# 05_MICROSD.net
KiCad netlist of a schematic drawn in Altium Designer
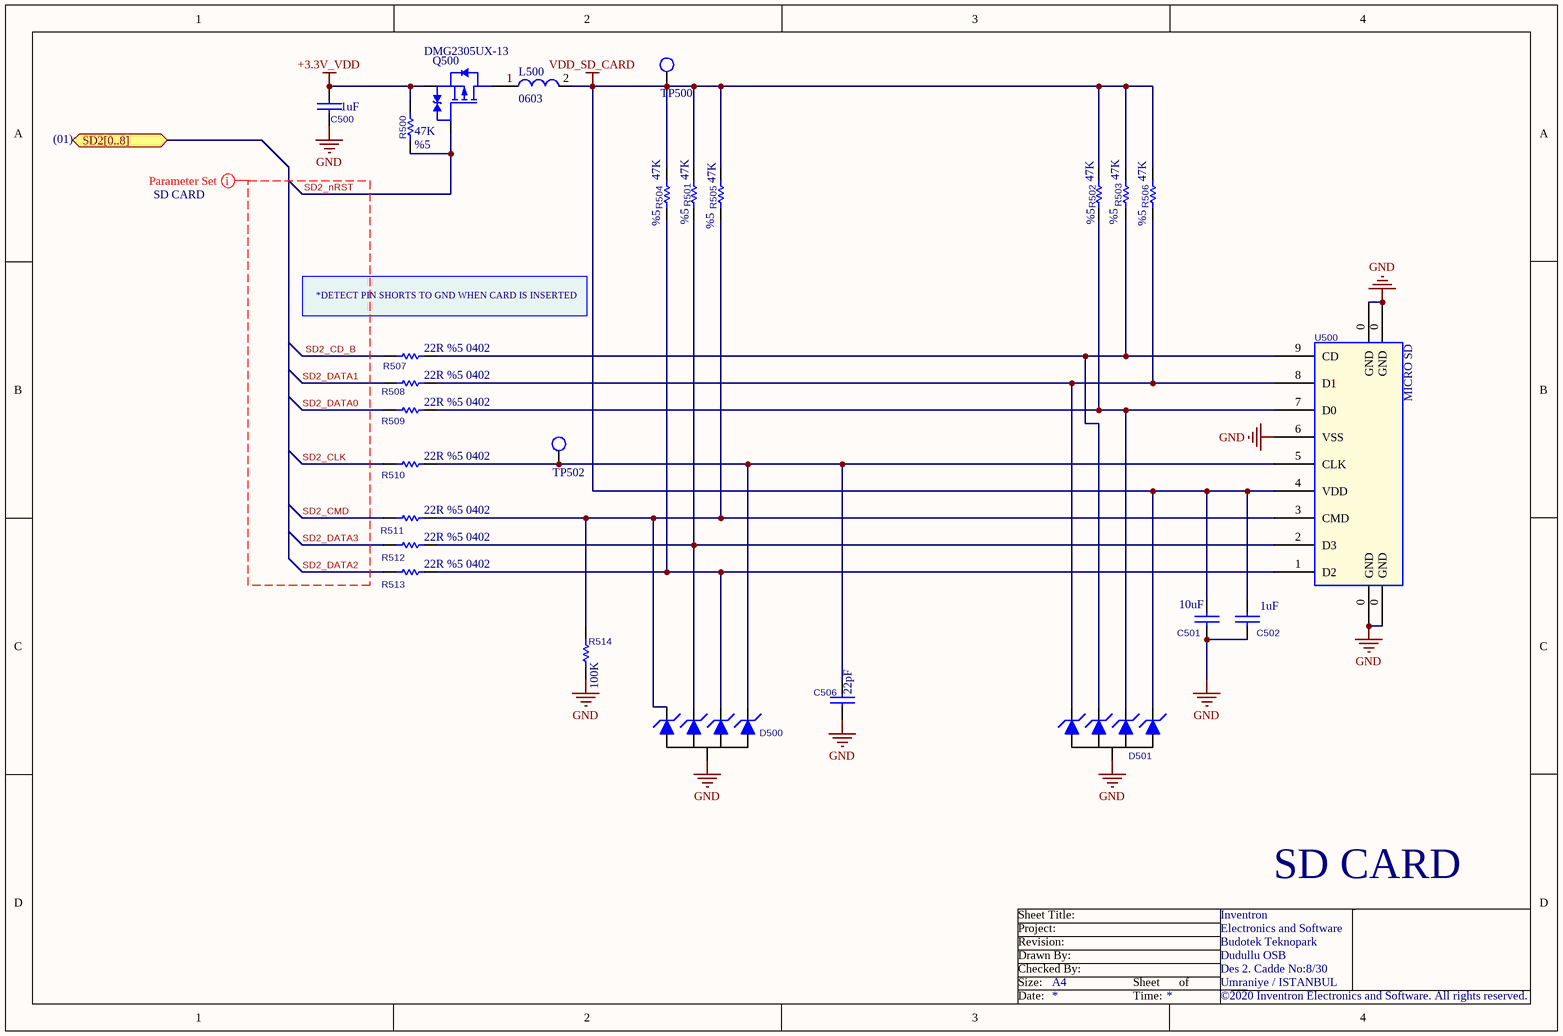
[diagram p0: 05 MICROSD.SchDoc]

(export (version "E")
  (design (tool "Eeschema 10.0.6"))
  (components
    (comp (ref "C500")
      (value "1uF")
      (footprint "0603_CC")
      (description "CAP CER 1UF 25V X7R 0603")
      (fields (field (name "CREATED BY") "LA") (field (name "CHECKED BY") "*"))
      (libsource (lib "ARETE_SCH") (part "CAP-CL10B105KA8NNNC"))
    )
    (comp (ref "C501")
      (value "10uF")
      (footprint "0603_CC")
      (description "CAP CER 10UF 6.3V X6S 0603")
      (fields (field (name "CREATED BY") "LA") (field (name "CHECKED BY") "*"))
      (libsource (lib "ARETE_SCH") (part "CAP-JMK107BC6106MA-T"))
    )
    (comp (ref "C502")
      (value "1uF")
      (footprint "0603_CC")
      (description "CAP CER 1UF 25V X7R 0603")
      (fields (field (name "CREATED BY") "LA") (field (name "CHECKED BY") "*"))
      (libsource (lib "ARETE_SCH") (part "CAP-CL10B105KA8NNNC"))
    )
    (comp (ref "C506")
      (value "22pF")
      (footprint "0402_CC")
      (description "CAP CER 22PF 50V C0G/NPO 0402")
      (fields (field (name "CREATED BY") "LA") (field (name "CHECKED BY") "*"))
      (libsource (lib "ARETE_SCH") (part "CAP-C0402C220K5GACTU"))
    )
    (comp (ref "D500")
      (value "DIODE-DF5A6.2LJE,LM")
      (footprint "DF5A6.2LJE,LM")
      (description "TVS DIODE 5V 4CH SOT-553")
      (fields (field (name "CREATED BY") "OKS") (field (name "CHECKED BY") "*"))
      (libsource (lib "ARETE_SCH") (part "DIODE-DF5A6.2LJE,LM"))
    )
    (comp (ref "D501")
      (value "DIODE-DF5A6.2LJE,LM")
      (footprint "DF5A6.2LJE,LM")
      (description "TVS DIODE 5V 4CH SOT-553")
      (fields (field (name "CREATED BY") "OKS") (field (name "CHECKED BY") "*"))
      (libsource (lib "ARETE_SCH") (part "DIODE-DF5A6.2LJE,LM"))
    )
    (comp (ref "L500")
      (value "0603")
      (footprint "0603_RES")
      (description "0OHM 0603")
      (fields (field (name "CREATED BY") "EE") (field (name "CHECKED BY") "*"))
      (libsource (lib "ARETE_SCH") (part "IND-FERRITE (RES 0 OHM) 0603"))
    )
    (comp (ref "Q500")
      (value "DMG2305UX-13")
      (footprint "SOT23")
      (description "MOSFET P-CH 20V 4.2A SOT23")
      (fields (field (name "CREATED BY") "EE") (field (name "CHECKED BY") "*"))
      (libsource (lib "ARETE_SCH") (part "MOS-DMG2305UX-13"))
    )
    (comp (ref "R500")
      (value "47K")
      (footprint "0402_RES")
      (description "RES 47K OHM 5% 1/16W 0402")
      (fields
        (field (name "TOLERANCE") "%5")
        (field (name "CREATED BY") "LA")
        (field (name "CHECKED BY") "*")
      )
      (libsource (lib "ARETE_SCH") (part "RES-47K"))
    )
    (comp (ref "R501")
      (value "47K")
      (footprint "0402_RES")
      (description "RES 47K OHM 5% 1/16W 0402")
      (fields
        (field (name "TOLERANCE") "%5")
        (field (name "CREATED BY") "LA")
        (field (name "CHECKED BY") "*")
      )
      (libsource (lib "ARETE_SCH") (part "RES-47K"))
    )
    (comp (ref "R502")
      (value "47K")
      (footprint "0402_RES")
      (description "RES 47K OHM 5% 1/16W 0402")
      (fields
        (field (name "TOLERANCE") "%5")
        (field (name "CREATED BY") "LA")
        (field (name "CHECKED BY") "*")
      )
      (libsource (lib "ARETE_SCH") (part "RES-47K"))
    )
    (comp (ref "R503")
      (value "47K")
      (footprint "0402_RES")
      (description "RES 47K OHM 5% 1/16W 0402")
      (fields
        (field (name "TOLERANCE") "%5")
        (field (name "CREATED BY") "LA")
        (field (name "CHECKED BY") "*")
      )
      (libsource (lib "ARETE_SCH") (part "RES-47K"))
    )
    (comp (ref "R504")
      (value "47K")
      (footprint "0402_RES")
      (description "RES 47K OHM 5% 1/16W 0402")
      (fields
        (field (name "TOLERANCE") "%5")
        (field (name "CREATED BY") "LA")
        (field (name "CHECKED BY") "*")
      )
      (libsource (lib "ARETE_SCH") (part "RES-47K"))
    )
    (comp (ref "R505")
      (value "47K")
      (footprint "0402_RES")
      (description "RES 47K OHM 5% 1/16W 0402")
      (fields
        (field (name "TOLERANCE") "%5")
        (field (name "CREATED BY") "LA")
        (field (name "CHECKED BY") "*")
      )
      (libsource (lib "ARETE_SCH") (part "RES-47K"))
    )
    (comp (ref "R506")
      (value "47K")
      (footprint "0402_RES")
      (description "RES 47K OHM 5% 1/16W 0402")
      (fields
        (field (name "TOLERANCE") "%5")
        (field (name "CREATED BY") "LA")
        (field (name "CHECKED BY") "*")
      )
      (libsource (lib "ARETE_SCH") (part "RES-47K"))
    )
    (comp (ref "R507")
      (value "22R %5 0402")
      (footprint "0402_RES")
      (description "RES, THICK FILM, 22R, 5%, 0.0625W, 0402, REEL")
      (fields (field (name "CREATED BY") "E.E") (field (name "CHECKED BY") "*"))
      (libsource (lib "ARETE_SCH") (part "RES- RC0402JR-0722RL."))
    )
    (comp (ref "R508")
      (value "22R %5 0402")
      (footprint "0402_RES")
      (description "RES, THICK FILM, 22R, 5%, 0.0625W, 0402, REEL")
      (fields (field (name "CREATED BY") "E.E") (field (name "CHECKED BY") "*"))
      (libsource (lib "ARETE_SCH") (part "RES- RC0402JR-0722RL."))
    )
    (comp (ref "R509")
      (value "22R %5 0402")
      (footprint "0402_RES")
      (description "RES, THICK FILM, 22R, 5%, 0.0625W, 0402, REEL")
      (fields (field (name "CREATED BY") "E.E") (field (name "CHECKED BY") "*"))
      (libsource (lib "ARETE_SCH") (part "RES- RC0402JR-0722RL."))
    )
    (comp (ref "R510")
      (value "22R %5 0402")
      (footprint "0402_RES")
      (description "RES, THICK FILM, 22R, 5%, 0.0625W, 0402, REEL")
      (fields (field (name "CREATED BY") "E.E") (field (name "CHECKED BY") "*"))
      (libsource (lib "ARETE_SCH") (part "RES- RC0402JR-0722RL."))
    )
    (comp (ref "R511")
      (value "22R %5 0402")
      (footprint "0402_RES")
      (description "RES, THICK FILM, 22R, 5%, 0.0625W, 0402, REEL")
      (fields (field (name "CREATED BY") "E.E") (field (name "CHECKED BY") "*"))
      (libsource (lib "ARETE_SCH") (part "RES- RC0402JR-0722RL."))
    )
    (comp (ref "R512")
      (value "22R %5 0402")
      (footprint "0402_RES")
      (description "RES, THICK FILM, 22R, 5%, 0.0625W, 0402, REEL")
      (fields (field (name "CREATED BY") "E.E") (field (name "CHECKED BY") "*"))
      (libsource (lib "ARETE_SCH") (part "RES- RC0402JR-0722RL."))
    )
    (comp (ref "R513")
      (value "22R %5 0402")
      (footprint "0402_RES")
      (description "RES, THICK FILM, 22R, 5%, 0.0625W, 0402, REEL")
      (fields (field (name "CREATED BY") "E.E") (field (name "CHECKED BY") "*"))
      (libsource (lib "ARETE_SCH") (part "RES- RC0402JR-0722RL."))
    )
    (comp (ref "R514")
      (value "100K")
      (footprint "0402_RES")
      (description "RES 100K OHM 5% 1/16W 0402")
      (fields
        (field (name "TOLERANCE") "%5")
        (field (name "CREATED BY") "LA")
        (field (name "CHECKED BY") "*")
      )
      (libsource (lib "ARETE_SCH") (part "RES-RMCF0402JT100K"))
    )
    (comp (ref "TP500")
      (value "TEST POINT 15")
      (footprint "testpoint_15")
      (libsource (lib "ARETE_L") (part "TEST POINT 15"))
    )
    (comp (ref "TP502")
      (value "TEST POINT 15")
      (footprint "testpoint_15")
      (libsource (lib "ARETE_L") (part "TEST POINT 15"))
    )
    (comp (ref "U500")
      (value "MICRO SD")
      (footprint "L-KLS1-TF-003-H1.85-R")
      (description "CONECTOR MICRO SD CARD SMD KLS")
      (fields (field (name "CREATED BY") "LA") (field (name "CHECKED BY") "*"))
      (libsource (lib "ARETE_SCH") (part "CON-L-KLS1-TF-003-H1.85-R"))
    )
  )
  (nets
    (net (code "10") (name "+3.3V_VDD") (class "Default")
      (node (ref "C500") (pin "1") (pinfunction "1_1") (pintype "passive"))
      (node (ref "Q500") (pin "2") (pinfunction "S_2") (pintype "passive"))
      (node (ref "R500") (pin "2") (pinfunction "2_2") (pintype "passive"))
    )
    (net (code "12") (name "/SD2_CD_B") (class "Default")
      (node (ref "R507") (pin "1") (pinfunction "1_1") (pintype "passive"))
    )
    (net (code "13") (name "/SD2_CLK") (class "Default")
      (node (ref "R510") (pin "1") (pinfunction "1_1") (pintype "passive"))
    )
    (net (code "14") (name "/SD2_CMD") (class "Default")
      (node (ref "R511") (pin "1") (pinfunction "1_1") (pintype "passive"))
    )
    (net (code "15") (name "/SD2_DATA0") (class "Default")
      (node (ref "R509") (pin "1") (pinfunction "1_1") (pintype "passive"))
    )
    (net (code "16") (name "/SD2_DATA1") (class "Default")
      (node (ref "R508") (pin "1") (pinfunction "1_1") (pintype "passive"))
    )
    (net (code "17") (name "/SD2_DATA2") (class "Default")
      (node (ref "R513") (pin "1") (pinfunction "1_1") (pintype "passive"))
    )
    (net (code "18") (name "/SD2_DATA3") (class "Default")
      (node (ref "R512") (pin "1") (pinfunction "1_1") (pintype "passive"))
    )
    (net (code "19") (name "/SD2_nRST") (class "Default")
      (node (ref "Q500") (pin "1") (pinfunction "G_1") (pintype "passive"))
      (node (ref "R500") (pin "1") (pinfunction "1_1") (pintype "passive"))
    )
    (net (code "20") (name "GND") (class "Default")
      (node (ref "C500") (pin "2") (pinfunction "2_2") (pintype "passive"))
      (node (ref "C501") (pin "2") (pinfunction "2_2") (pintype "passive"))
      (node (ref "C502") (pin "2") (pinfunction "2_2") (pintype "passive"))
      (node (ref "C506") (pin "2") (pinfunction "2_2") (pintype "passive"))
      (node (ref "D500") (pin "2") (pinfunction "2_2") (pintype "passive"))
      (node (ref "D501") (pin "2") (pinfunction "2_2") (pintype "passive"))
      (node (ref "R514") (pin "1") (pinfunction "1_1") (pintype "passive"))
      (node (ref "U500") (pin "0") (pinfunction "GND_0") (pintype "passive"))
      (node (ref "U500") (pin "6") (pinfunction "VSS_6") (pintype "passive"))
    )
    (net (code "21") (name "Net-(Q500-D)") (class "Default")
      (node (ref "L500") (pin "1") (pinfunction "1_1") (pintype "passive"))
      (node (ref "Q500") (pin "3") (pinfunction "D_3") (pintype "passive"))
    )
    (net (code "22") (name "Net-(U500-CD)") (class "Default")
      (node (ref "D501") (pin "3") (pinfunction "3_3") (pintype "passive"))
      (node (ref "R503") (pin "1") (pinfunction "1_1") (pintype "passive"))
      (node (ref "R507") (pin "2") (pinfunction "2_2") (pintype "passive"))
      (node (ref "U500") (pin "9") (pinfunction "CD_9") (pintype "passive"))
    )
    (net (code "23") (name "Net-(U500-CLK)") (class "Default")
      (node (ref "C506") (pin "1") (pinfunction "1_1") (pintype "passive"))
      (node (ref "D500") (pin "5") (pinfunction "5_5") (pintype "passive"))
      (node (ref "R510") (pin "2") (pinfunction "2_2") (pintype "passive"))
      (node (ref "TP502") (pin "1") (pinfunction "1_1") (pintype "passive"))
      (node (ref "U500") (pin "5") (pinfunction "CLK_5") (pintype "passive"))
    )
    (net (code "24") (name "Net-(U500-CMD)") (class "Default")
      (node (ref "D500") (pin "1") (pinfunction "1_1") (pintype "passive"))
      (node (ref "R505") (pin "1") (pinfunction "1_1") (pintype "passive"))
      (node (ref "R511") (pin "2") (pinfunction "2_2") (pintype "passive"))
      (node (ref "R514") (pin "2") (pinfunction "2_2") (pintype "passive"))
      (node (ref "U500") (pin "3") (pinfunction "CMD_3") (pintype "passive"))
    )
    (net (code "25") (name "Net-(U500-D0)") (class "Default")
      (node (ref "D501") (pin "4") (pinfunction "4_4") (pintype "passive"))
      (node (ref "R502") (pin "1") (pinfunction "1_1") (pintype "passive"))
      (node (ref "R509") (pin "2") (pinfunction "2_2") (pintype "passive"))
      (node (ref "U500") (pin "7") (pinfunction "D0_7") (pintype "passive"))
    )
    (net (code "26") (name "Net-(U500-D1)") (class "Default")
      (node (ref "D501") (pin "1") (pinfunction "1_1") (pintype "passive"))
      (node (ref "R506") (pin "1") (pinfunction "1_1") (pintype "passive"))
      (node (ref "R508") (pin "2") (pinfunction "2_2") (pintype "passive"))
      (node (ref "U500") (pin "8") (pinfunction "D1_8") (pintype "passive"))
    )
    (net (code "27") (name "Net-(U500-D2)") (class "Default")
      (node (ref "D500") (pin "4") (pinfunction "4_4") (pintype "passive"))
      (node (ref "R504") (pin "1") (pinfunction "1_1") (pintype "passive"))
      (node (ref "R513") (pin "2") (pinfunction "2_2") (pintype "passive"))
      (node (ref "U500") (pin "1") (pinfunction "D2_1") (pintype "passive"))
    )
    (net (code "28") (name "Net-(U500-D3)") (class "Default")
      (node (ref "D500") (pin "3") (pinfunction "3_3") (pintype "passive"))
      (node (ref "R501") (pin "1") (pinfunction "1_1") (pintype "passive"))
      (node (ref "R512") (pin "2") (pinfunction "2_2") (pintype "passive"))
      (node (ref "U500") (pin "2") (pinfunction "D3_2") (pintype "passive"))
    )
    (net (code "29") (name "VDD_SD_CARD") (class "Default")
      (node (ref "C501") (pin "1") (pinfunction "1_1") (pintype "passive"))
      (node (ref "C502") (pin "1") (pinfunction "1_1") (pintype "passive"))
      (node (ref "D501") (pin "5") (pinfunction "5_5") (pintype "passive"))
      (node (ref "L500") (pin "2") (pinfunction "2_2") (pintype "passive"))
      (node (ref "R501") (pin "2") (pinfunction "2_2") (pintype "passive"))
      (node (ref "R502") (pin "2") (pinfunction "2_2") (pintype "passive"))
      (node (ref "R503") (pin "2") (pinfunction "2_2") (pintype "passive"))
      (node (ref "R504") (pin "2") (pinfunction "2_2") (pintype "passive"))
      (node (ref "R505") (pin "2") (pinfunction "2_2") (pintype "passive"))
      (node (ref "R506") (pin "2") (pinfunction "2_2") (pintype "passive"))
      (node (ref "TP500") (pin "1") (pinfunction "1_1") (pintype "passive"))
      (node (ref "U500") (pin "4") (pinfunction "VDD_4") (pintype "passive"))
    )
  )
)
